# Zio_16_Servo_Controller.net
KiCad netlist of a schematic drawn in EAGLE
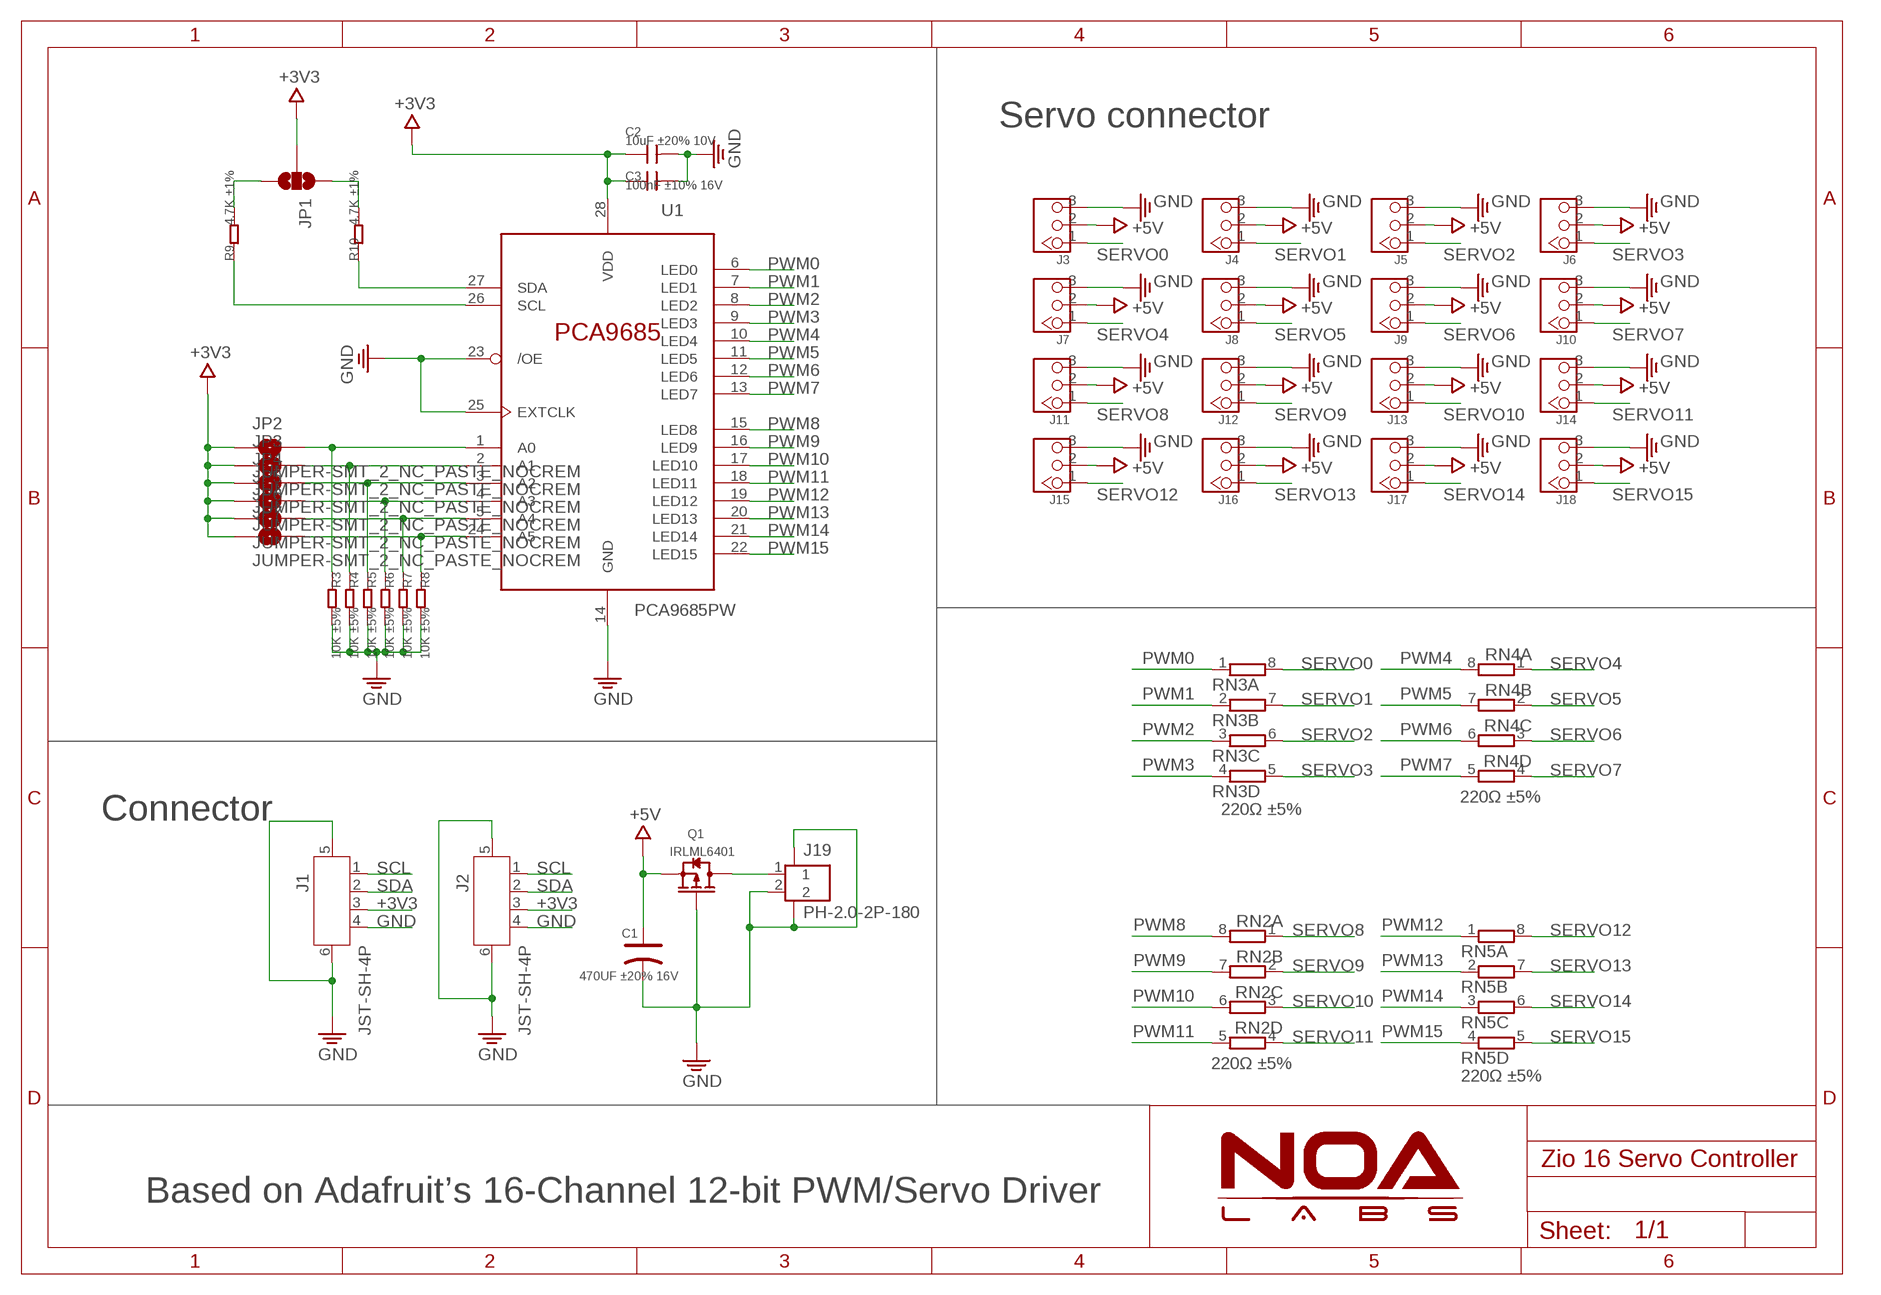
[diagram p0: schematic, sheet 1]

(export (version "E")
  (design (tool "Eeschema 10.0.6"))
  (components
    (comp (ref "C1")
      (value "470UF ±20% 16V")
      (footprint "eagle-import:ELECTRO-SMD-E-7.8MM")
      (libsource (lib "eagle-import") (part "CAP-ELECTRO-E"))
    )
    (comp (ref "C2")
      (value "10uF ±20% 10V")
      (footprint "eagle-import:0402")
      (libsource (lib "eagle-import") (part "C-0402"))
    )
    (comp (ref "C3")
      (value "100nF ±10% 16V")
      (footprint "eagle-import:0402")
      (libsource (lib "eagle-import") (part "C-0402"))
    )
    (comp (ref "J1")
      (value "JST-SH-4P")
      (footprint "eagle-import:JST-SH-4P-90")
      (libsource (lib "eagle-import") (part "JST-SH-4P"))
    )
    (comp (ref "J2")
      (value "JST-SH-4P")
      (footprint "eagle-import:JST-SH-4P-90")
      (libsource (lib "eagle-import") (part "JST-SH-4P"))
    )
    (comp (ref "J3")
      (value "HEADER-3P-2.54")
      (footprint "eagle-import:3P-2.54")
      (libsource (lib "eagle-import") (part "HEADER-3P-2.54"))
    )
    (comp (ref "J4")
      (value "HEADER-3P-2.54")
      (footprint "eagle-import:3P-2.54")
      (libsource (lib "eagle-import") (part "HEADER-3P-2.54"))
    )
    (comp (ref "J5")
      (value "HEADER-3P-2.54")
      (footprint "eagle-import:3P-2.54")
      (libsource (lib "eagle-import") (part "HEADER-3P-2.54"))
    )
    (comp (ref "J6")
      (value "HEADER-3P-2.54")
      (footprint "eagle-import:3P-2.54")
      (libsource (lib "eagle-import") (part "HEADER-3P-2.54"))
    )
    (comp (ref "J7")
      (value "HEADER-3P-2.54")
      (footprint "eagle-import:3P-2.54")
      (libsource (lib "eagle-import") (part "HEADER-3P-2.54"))
    )
    (comp (ref "J8")
      (value "HEADER-3P-2.54")
      (footprint "eagle-import:3P-2.54")
      (libsource (lib "eagle-import") (part "HEADER-3P-2.54"))
    )
    (comp (ref "J9")
      (value "HEADER-3P-2.54")
      (footprint "eagle-import:3P-2.54")
      (libsource (lib "eagle-import") (part "HEADER-3P-2.54"))
    )
    (comp (ref "J10")
      (value "HEADER-3P-2.54")
      (footprint "eagle-import:3P-2.54")
      (libsource (lib "eagle-import") (part "HEADER-3P-2.54"))
    )
    (comp (ref "J11")
      (value "HEADER-3P-2.54")
      (footprint "eagle-import:3P-2.54")
      (libsource (lib "eagle-import") (part "HEADER-3P-2.54"))
    )
    (comp (ref "J12")
      (value "HEADER-3P-2.54")
      (footprint "eagle-import:3P-2.54")
      (libsource (lib "eagle-import") (part "HEADER-3P-2.54"))
    )
    (comp (ref "J13")
      (value "HEADER-3P-2.54")
      (footprint "eagle-import:3P-2.54")
      (libsource (lib "eagle-import") (part "HEADER-3P-2.54"))
    )
    (comp (ref "J14")
      (value "HEADER-3P-2.54")
      (footprint "eagle-import:3P-2.54")
      (libsource (lib "eagle-import") (part "HEADER-3P-2.54"))
    )
    (comp (ref "J15")
      (value "HEADER-3P-2.54")
      (footprint "eagle-import:3P-2.54")
      (libsource (lib "eagle-import") (part "HEADER-3P-2.54"))
    )
    (comp (ref "J16")
      (value "HEADER-3P-2.54")
      (footprint "eagle-import:3P-2.54")
      (libsource (lib "eagle-import") (part "HEADER-3P-2.54"))
    )
    (comp (ref "J17")
      (value "HEADER-3P-2.54")
      (footprint "eagle-import:3P-2.54")
      (libsource (lib "eagle-import") (part "HEADER-3P-2.54"))
    )
    (comp (ref "J18")
      (value "HEADER-3P-2.54")
      (footprint "eagle-import:3P-2.54")
      (libsource (lib "eagle-import") (part "HEADER-3P-2.54"))
    )
    (comp (ref "J19")
      (value "PH-2.0-2P-180")
      (footprint "eagle-import:PH2.0_2P_180")
      (libsource (lib "eagle-import") (part "PH-2.0-2P-180"))
    )
    (comp (ref "JP1")
      (value "JUMPER-SMT_3_2-NC_PASTE_NOCREM")
      (footprint "eagle-import:SMT-JUMPER_3_2-NC_PASTE_SILK_NOCREM")
      (libsource (lib "eagle-import") (part "JUMPER-SMT_3_2-NC_PASTE_NOCREM"))
    )
    (comp (ref "JP2")
      (value "JUMPER-SMT_2_NC_PASTE_NOCREM")
      (footprint "eagle-import:SMT-JUMPER_2_NC_PASTE_SILK_NOCREM")
      (libsource (lib "eagle-import") (part "JUMPER-SMT_2_NC_PASTE_NOCREM"))
    )
    (comp (ref "JP3")
      (value "JUMPER-SMT_2_NC_PASTE_NOCREM")
      (footprint "eagle-import:SMT-JUMPER_2_NC_PASTE_SILK_NOCREM")
      (libsource (lib "eagle-import") (part "JUMPER-SMT_2_NC_PASTE_NOCREM"))
    )
    (comp (ref "JP4")
      (value "JUMPER-SMT_2_NC_PASTE_NOCREM")
      (footprint "eagle-import:SMT-JUMPER_2_NC_PASTE_SILK_NOCREM")
      (libsource (lib "eagle-import") (part "JUMPER-SMT_2_NC_PASTE_NOCREM"))
    )
    (comp (ref "JP5")
      (value "JUMPER-SMT_2_NC_PASTE_NOCREM")
      (footprint "eagle-import:SMT-JUMPER_2_NC_PASTE_SILK_NOCREM")
      (libsource (lib "eagle-import") (part "JUMPER-SMT_2_NC_PASTE_NOCREM"))
    )
    (comp (ref "JP6")
      (value "JUMPER-SMT_2_NC_PASTE_NOCREM")
      (footprint "eagle-import:SMT-JUMPER_2_NC_PASTE_SILK_NOCREM")
      (libsource (lib "eagle-import") (part "JUMPER-SMT_2_NC_PASTE_NOCREM"))
    )
    (comp (ref "JP7")
      (value "JUMPER-SMT_2_NC_PASTE_NOCREM")
      (footprint "eagle-import:SMT-JUMPER_2_NC_PASTE_SILK_NOCREM")
      (libsource (lib "eagle-import") (part "JUMPER-SMT_2_NC_PASTE_NOCREM"))
    )
    (comp (ref "Q1")
      (value "IRLML6401")
      (footprint "eagle-import:SOT23")
      (libsource (lib "eagle-import") (part "MOSFET-P-SOT23"))
    )
    (comp (ref "R3")
      (value "10K ±5%")
      (footprint "eagle-import:0402")
      (libsource (lib "eagle-import") (part "R-0402"))
    )
    (comp (ref "R4")
      (value "10K ±5%")
      (footprint "eagle-import:0402")
      (libsource (lib "eagle-import") (part "R-0402"))
    )
    (comp (ref "R5")
      (value "10K ±5%")
      (footprint "eagle-import:0402")
      (libsource (lib "eagle-import") (part "R-0402"))
    )
    (comp (ref "R6")
      (value "10K ±5%")
      (footprint "eagle-import:0402")
      (libsource (lib "eagle-import") (part "R-0402"))
    )
    (comp (ref "R7")
      (value "10K ±5%")
      (footprint "eagle-import:0402")
      (libsource (lib "eagle-import") (part "R-0402"))
    )
    (comp (ref "R8")
      (value "10K ±5%")
      (footprint "eagle-import:0402")
      (libsource (lib "eagle-import") (part "R-0402"))
    )
    (comp (ref "R9")
      (value "4.7K ±1%")
      (footprint "eagle-import:0402")
      (libsource (lib "eagle-import") (part "Discretex_R-0402"))
    )
    (comp (ref "R10")
      (value "4.7K ±1%")
      (footprint "eagle-import:0402")
      (libsource (lib "eagle-import") (part "Discretex_R-0402"))
    )
    (comp (ref "RN2")
      (value "220Ω ±5%")
      (footprint "eagle-import:RESISTOR-DIL_0603-ARV")
      (libsource (lib "eagle-import") (part "RESISTOR-DIL_4R-N0603-ARV"))
    )
    (comp (ref "RN3")
      (value "220Ω ±5%")
      (footprint "eagle-import:RESISTOR-DIL_0603-ARV")
      (libsource (lib "eagle-import") (part "RESISTOR-DIL_4R-N0603-ARV"))
    )
    (comp (ref "RN4")
      (value "220Ω ±5%")
      (footprint "eagle-import:RESISTOR-DIL_0603-ARV")
      (libsource (lib "eagle-import") (part "RESISTOR-DIL_4R-N0603-ARV"))
    )
    (comp (ref "RN5")
      (value "220Ω ±5%")
      (footprint "eagle-import:RESISTOR-DIL_0603-ARV")
      (libsource (lib "eagle-import") (part "RESISTOR-DIL_4R-N0603-ARV"))
    )
    (comp (ref "U1")
      (value "PCA9685PW")
      (footprint "eagle-import:TSSOP28")
      (libsource (lib "eagle-import") (part "PCA9685PW"))
    )
  )
  (nets
    (net (code "1") (name "+3V3") (class "Default")
      (node (ref "C2") (pin "1") (pinfunction "1_1") (pintype "passive"))
      (node (ref "C3") (pin "1") (pinfunction "1_1") (pintype "passive"))
      (node (ref "J1") (pin "3") (pinfunction "3_3") (pintype "bidirectional"))
      (node (ref "J2") (pin "3") (pinfunction "3_3") (pintype "bidirectional"))
      (node (ref "JP1") (pin "2") (pinfunction "2_2") (pintype "passive"))
      (node (ref "JP2") (pin "1") (pinfunction "1_1") (pintype "passive"))
      (node (ref "JP3") (pin "1") (pinfunction "1_1") (pintype "passive"))
      (node (ref "JP4") (pin "1") (pinfunction "1_1") (pintype "passive"))
      (node (ref "JP5") (pin "1") (pinfunction "1_1") (pintype "passive"))
      (node (ref "JP6") (pin "1") (pinfunction "1_1") (pintype "passive"))
      (node (ref "JP7") (pin "1") (pinfunction "1_1") (pintype "passive"))
      (node (ref "U1") (pin "28") (pinfunction "VDD_28") (pintype "power_in"))
    )
    (net (code "2") (name "+5V") (class "Default")
      (node (ref "C1") (pin "+") (pinfunction "+_+") (pintype "passive"))
      (node (ref "J10") (pin "2") (pinfunction "P$2_2") (pintype "bidirectional"))
      (node (ref "J11") (pin "2") (pinfunction "P$2_2") (pintype "bidirectional"))
      (node (ref "J12") (pin "2") (pinfunction "P$2_2") (pintype "bidirectional"))
      (node (ref "J13") (pin "2") (pinfunction "P$2_2") (pintype "bidirectional"))
      (node (ref "J14") (pin "2") (pinfunction "P$2_2") (pintype "bidirectional"))
      (node (ref "J15") (pin "2") (pinfunction "P$2_2") (pintype "bidirectional"))
      (node (ref "J16") (pin "2") (pinfunction "P$2_2") (pintype "bidirectional"))
      (node (ref "J17") (pin "2") (pinfunction "P$2_2") (pintype "bidirectional"))
      (node (ref "J18") (pin "2") (pinfunction "P$2_2") (pintype "bidirectional"))
      (node (ref "J3") (pin "2") (pinfunction "P$2_2") (pintype "bidirectional"))
      (node (ref "J4") (pin "2") (pinfunction "P$2_2") (pintype "bidirectional"))
      (node (ref "J5") (pin "2") (pinfunction "P$2_2") (pintype "bidirectional"))
      (node (ref "J6") (pin "2") (pinfunction "P$2_2") (pintype "bidirectional"))
      (node (ref "J7") (pin "2") (pinfunction "P$2_2") (pintype "bidirectional"))
      (node (ref "J8") (pin "2") (pinfunction "P$2_2") (pintype "bidirectional"))
      (node (ref "J9") (pin "2") (pinfunction "P$2_2") (pintype "bidirectional"))
      (node (ref "Q1") (pin "2") (pinfunction "S_2") (pintype "passive"))
    )
    (net (code "3") (name "/PWM0") (class "Default")
      (node (ref "RN3") (pin "1") (pinfunction "1_1") (pintype "passive"))
      (node (ref "U1") (pin "6") (pinfunction "LED0_6") (pintype "bidirectional"))
    )
    (net (code "4") (name "/PWM1") (class "Default")
      (node (ref "RN3") (pin "2") (pinfunction "1_2") (pintype "passive"))
      (node (ref "U1") (pin "7") (pinfunction "LED1_7") (pintype "bidirectional"))
    )
    (net (code "5") (name "/PWM2") (class "Default")
      (node (ref "RN3") (pin "3") (pinfunction "1_3") (pintype "passive"))
      (node (ref "U1") (pin "8") (pinfunction "LED2_8") (pintype "bidirectional"))
    )
    (net (code "6") (name "/PWM3") (class "Default")
      (node (ref "RN3") (pin "4") (pinfunction "1_4") (pintype "passive"))
      (node (ref "U1") (pin "9") (pinfunction "LED3_9") (pintype "bidirectional"))
    )
    (net (code "7") (name "/PWM4") (class "Default")
      (node (ref "RN4") (pin "8") (pinfunction "2_8") (pintype "passive"))
      (node (ref "U1") (pin "10") (pinfunction "LED4_10") (pintype "bidirectional"))
    )
    (net (code "8") (name "/PWM5") (class "Default")
      (node (ref "RN4") (pin "7") (pinfunction "2_7") (pintype "passive"))
      (node (ref "U1") (pin "11") (pinfunction "LED5_11") (pintype "bidirectional"))
    )
    (net (code "9") (name "/PWM6") (class "Default")
      (node (ref "RN4") (pin "6") (pinfunction "2_6") (pintype "passive"))
      (node (ref "U1") (pin "12") (pinfunction "LED6_12") (pintype "bidirectional"))
    )
    (net (code "10") (name "/PWM7") (class "Default")
      (node (ref "RN4") (pin "5") (pinfunction "2_5") (pintype "passive"))
      (node (ref "U1") (pin "13") (pinfunction "LED7_13") (pintype "bidirectional"))
    )
    (net (code "11") (name "/PWM8") (class "Default")
      (node (ref "RN2") (pin "8") (pinfunction "2_8") (pintype "passive"))
      (node (ref "U1") (pin "15") (pinfunction "LED8_15") (pintype "bidirectional"))
    )
    (net (code "12") (name "/PWM9") (class "Default")
      (node (ref "RN2") (pin "7") (pinfunction "2_7") (pintype "passive"))
      (node (ref "U1") (pin "16") (pinfunction "LED9_16") (pintype "bidirectional"))
    )
    (net (code "13") (name "/PWM10") (class "Default")
      (node (ref "RN2") (pin "6") (pinfunction "2_6") (pintype "passive"))
      (node (ref "U1") (pin "17") (pinfunction "LED10_17") (pintype "bidirectional"))
    )
    (net (code "14") (name "/PWM11") (class "Default")
      (node (ref "RN2") (pin "5") (pinfunction "2_5") (pintype "passive"))
      (node (ref "U1") (pin "18") (pinfunction "LED11_18") (pintype "bidirectional"))
    )
    (net (code "15") (name "/PWM12") (class "Default")
      (node (ref "RN5") (pin "1") (pinfunction "1_1") (pintype "passive"))
      (node (ref "U1") (pin "19") (pinfunction "LED12_19") (pintype "bidirectional"))
    )
    (net (code "16") (name "/PWM13") (class "Default")
      (node (ref "RN5") (pin "2") (pinfunction "1_2") (pintype "passive"))
      (node (ref "U1") (pin "20") (pinfunction "LED13_20") (pintype "bidirectional"))
    )
    (net (code "17") (name "/PWM14") (class "Default")
      (node (ref "RN5") (pin "3") (pinfunction "1_3") (pintype "passive"))
      (node (ref "U1") (pin "21") (pinfunction "LED14_21") (pintype "bidirectional"))
    )
    (net (code "18") (name "/PWM15") (class "Default")
      (node (ref "RN5") (pin "4") (pinfunction "1_4") (pintype "passive"))
      (node (ref "U1") (pin "22") (pinfunction "LED15_22") (pintype "bidirectional"))
    )
    (net (code "19") (name "/SCL") (class "Default")
      (node (ref "J1") (pin "1") (pinfunction "1_1") (pintype "bidirectional"))
      (node (ref "J2") (pin "1") (pinfunction "1_1") (pintype "bidirectional"))
      (node (ref "R9") (pin "1") (pinfunction "1_1") (pintype "passive"))
      (node (ref "U1") (pin "26") (pinfunction "SCL_26") (pintype "bidirectional"))
    )
    (net (code "20") (name "/SDA") (class "Default")
      (node (ref "J1") (pin "2") (pinfunction "2_2") (pintype "bidirectional"))
      (node (ref "J2") (pin "2") (pinfunction "2_2") (pintype "bidirectional"))
      (node (ref "R10") (pin "1") (pinfunction "1_1") (pintype "passive"))
      (node (ref "U1") (pin "27") (pinfunction "SDA_27") (pintype "bidirectional"))
    )
    (net (code "21") (name "/SERVO0") (class "Default")
      (node (ref "J3") (pin "1") (pinfunction "P$1_1") (pintype "bidirectional"))
      (node (ref "RN3") (pin "8") (pinfunction "2_8") (pintype "passive"))
    )
    (net (code "22") (name "/SERVO1") (class "Default")
      (node (ref "J4") (pin "1") (pinfunction "P$1_1") (pintype "bidirectional"))
      (node (ref "RN3") (pin "7") (pinfunction "2_7") (pintype "passive"))
    )
    (net (code "23") (name "/SERVO2") (class "Default")
      (node (ref "J5") (pin "1") (pinfunction "P$1_1") (pintype "bidirectional"))
      (node (ref "RN3") (pin "6") (pinfunction "2_6") (pintype "passive"))
    )
    (net (code "24") (name "/SERVO3") (class "Default")
      (node (ref "J6") (pin "1") (pinfunction "P$1_1") (pintype "bidirectional"))
      (node (ref "RN3") (pin "5") (pinfunction "2_5") (pintype "passive"))
    )
    (net (code "25") (name "/SERVO4") (class "Default")
      (node (ref "J7") (pin "1") (pinfunction "P$1_1") (pintype "bidirectional"))
      (node (ref "RN4") (pin "1") (pinfunction "1_1") (pintype "passive"))
    )
    (net (code "26") (name "/SERVO5") (class "Default")
      (node (ref "J8") (pin "1") (pinfunction "P$1_1") (pintype "bidirectional"))
      (node (ref "RN4") (pin "2") (pinfunction "1_2") (pintype "passive"))
    )
    (net (code "27") (name "/SERVO6") (class "Default")
      (node (ref "J9") (pin "1") (pinfunction "P$1_1") (pintype "bidirectional"))
      (node (ref "RN4") (pin "3") (pinfunction "1_3") (pintype "passive"))
    )
    (net (code "28") (name "/SERVO7") (class "Default")
      (node (ref "J10") (pin "1") (pinfunction "P$1_1") (pintype "bidirectional"))
      (node (ref "RN4") (pin "4") (pinfunction "1_4") (pintype "passive"))
    )
    (net (code "29") (name "/SERVO8") (class "Default")
      (node (ref "J11") (pin "1") (pinfunction "P$1_1") (pintype "bidirectional"))
      (node (ref "RN2") (pin "1") (pinfunction "1_1") (pintype "passive"))
    )
    (net (code "30") (name "/SERVO9") (class "Default")
      (node (ref "J12") (pin "1") (pinfunction "P$1_1") (pintype "bidirectional"))
      (node (ref "RN2") (pin "2") (pinfunction "1_2") (pintype "passive"))
    )
    (net (code "31") (name "/SERVO10") (class "Default")
      (node (ref "J13") (pin "1") (pinfunction "P$1_1") (pintype "bidirectional"))
      (node (ref "RN2") (pin "3") (pinfunction "1_3") (pintype "passive"))
    )
    (net (code "32") (name "/SERVO11") (class "Default")
      (node (ref "J14") (pin "1") (pinfunction "P$1_1") (pintype "bidirectional"))
      (node (ref "RN2") (pin "4") (pinfunction "1_4") (pintype "passive"))
    )
    (net (code "33") (name "/SERVO12") (class "Default")
      (node (ref "J15") (pin "1") (pinfunction "P$1_1") (pintype "bidirectional"))
      (node (ref "RN5") (pin "8") (pinfunction "2_8") (pintype "passive"))
    )
    (net (code "34") (name "/SERVO13") (class "Default")
      (node (ref "J16") (pin "1") (pinfunction "P$1_1") (pintype "bidirectional"))
      (node (ref "RN5") (pin "7") (pinfunction "2_7") (pintype "passive"))
    )
    (net (code "35") (name "/SERVO14") (class "Default")
      (node (ref "J17") (pin "1") (pinfunction "P$1_1") (pintype "bidirectional"))
      (node (ref "RN5") (pin "6") (pinfunction "2_6") (pintype "passive"))
    )
    (net (code "36") (name "/SERVO15") (class "Default")
      (node (ref "J18") (pin "1") (pinfunction "P$1_1") (pintype "bidirectional"))
      (node (ref "RN5") (pin "5") (pinfunction "2_5") (pintype "passive"))
    )
    (net (code "37") (name "GND") (class "Default")
      (node (ref "C1") (pin "-") (pinfunction "-_-") (pintype "passive"))
      (node (ref "C2") (pin "2") (pinfunction "2_2") (pintype "passive"))
      (node (ref "C3") (pin "2") (pinfunction "2_2") (pintype "passive"))
      (node (ref "J1") (pin "4") (pinfunction "4_4") (pintype "bidirectional"))
      (node (ref "J1") (pin "5") (pinfunction "5_5") (pintype "bidirectional"))
      (node (ref "J1") (pin "6") (pinfunction "6_6") (pintype "bidirectional"))
      (node (ref "J10") (pin "3") (pinfunction "P$3_3") (pintype "bidirectional"))
      (node (ref "J11") (pin "3") (pinfunction "P$3_3") (pintype "bidirectional"))
      (node (ref "J12") (pin "3") (pinfunction "P$3_3") (pintype "bidirectional"))
      (node (ref "J13") (pin "3") (pinfunction "P$3_3") (pintype "bidirectional"))
      (node (ref "J14") (pin "3") (pinfunction "P$3_3") (pintype "bidirectional"))
      (node (ref "J15") (pin "3") (pinfunction "P$3_3") (pintype "bidirectional"))
      (node (ref "J16") (pin "3") (pinfunction "P$3_3") (pintype "bidirectional"))
      (node (ref "J17") (pin "3") (pinfunction "P$3_3") (pintype "bidirectional"))
      (node (ref "J18") (pin "3") (pinfunction "P$3_3") (pintype "bidirectional"))
      (node (ref "J19") (pin "2") (pinfunction "2_2") (pintype "bidirectional"))
      (node (ref "J19") (pin "3") (pinfunction "3_3") (pintype "bidirectional"))
      (node (ref "J19") (pin "4") (pinfunction "4_4") (pintype "bidirectional"))
      (node (ref "J2") (pin "4") (pinfunction "4_4") (pintype "bidirectional"))
      (node (ref "J2") (pin "5") (pinfunction "5_5") (pintype "bidirectional"))
      (node (ref "J2") (pin "6") (pinfunction "6_6") (pintype "bidirectional"))
      (node (ref "J3") (pin "3") (pinfunction "P$3_3") (pintype "bidirectional"))
      (node (ref "J4") (pin "3") (pinfunction "P$3_3") (pintype "bidirectional"))
      (node (ref "J5") (pin "3") (pinfunction "P$3_3") (pintype "bidirectional"))
      (node (ref "J6") (pin "3") (pinfunction "P$3_3") (pintype "bidirectional"))
      (node (ref "J7") (pin "3") (pinfunction "P$3_3") (pintype "bidirectional"))
      (node (ref "J8") (pin "3") (pinfunction "P$3_3") (pintype "bidirectional"))
      (node (ref "J9") (pin "3") (pinfunction "P$3_3") (pintype "bidirectional"))
      (node (ref "Q1") (pin "1") (pinfunction "G_1") (pintype "passive"))
      (node (ref "R3") (pin "2") (pinfunction "2_2") (pintype "passive"))
      (node (ref "R4") (pin "2") (pinfunction "2_2") (pintype "passive"))
      (node (ref "R5") (pin "2") (pinfunction "2_2") (pintype "passive"))
      (node (ref "R6") (pin "2") (pinfunction "2_2") (pintype "passive"))
      (node (ref "R7") (pin "2") (pinfunction "2_2") (pintype "passive"))
      (node (ref "R8") (pin "2") (pinfunction "2_2") (pintype "passive"))
      (node (ref "U1") (pin "14") (pinfunction "GND_14") (pintype "power_in"))
      (node (ref "U1") (pin "23") (pinfunction "/OE_23") (pintype "bidirectional"))
      (node (ref "U1") (pin "25") (pinfunction "EXTCLK_25") (pintype "input"))
    )
    (net (code "38") (name "Net-(JP1-Pad1)") (class "Default")
      (node (ref "JP1") (pin "1") (pinfunction "1_1") (pintype "passive"))
      (node (ref "R10") (pin "2") (pinfunction "2_2") (pintype "passive"))
    )
    (net (code "39") (name "Net-(JP1-Pad3)") (class "Default")
      (node (ref "JP1") (pin "3") (pinfunction "3_3") (pintype "passive"))
      (node (ref "R9") (pin "2") (pinfunction "2_2") (pintype "passive"))
    )
    (net (code "40") (name "Net-(Q1-D)") (class "Default")
      (node (ref "J19") (pin "1") (pinfunction "1_1") (pintype "bidirectional"))
      (node (ref "Q1") (pin "3") (pinfunction "D_3") (pintype "passive"))
    )
    (net (code "41") (name "Net-(U1-A0)") (class "Default")
      (node (ref "JP2") (pin "2") (pinfunction "2_2") (pintype "passive"))
      (node (ref "R3") (pin "1") (pinfunction "1_1") (pintype "passive"))
      (node (ref "U1") (pin "1") (pinfunction "A0_1") (pintype "bidirectional"))
    )
    (net (code "42") (name "Net-(U1-A1)") (class "Default")
      (node (ref "JP3") (pin "2") (pinfunction "2_2") (pintype "passive"))
      (node (ref "R4") (pin "1") (pinfunction "1_1") (pintype "passive"))
      (node (ref "U1") (pin "2") (pinfunction "A1_2") (pintype "bidirectional"))
    )
    (net (code "43") (name "Net-(U1-A2)") (class "Default")
      (node (ref "JP4") (pin "2") (pinfunction "2_2") (pintype "passive"))
      (node (ref "R5") (pin "1") (pinfunction "1_1") (pintype "passive"))
      (node (ref "U1") (pin "3") (pinfunction "A2_3") (pintype "bidirectional"))
    )
    (net (code "44") (name "Net-(U1-A3)") (class "Default")
      (node (ref "JP5") (pin "2") (pinfunction "2_2") (pintype "passive"))
      (node (ref "R6") (pin "1") (pinfunction "1_1") (pintype "passive"))
      (node (ref "U1") (pin "4") (pinfunction "A3_4") (pintype "bidirectional"))
    )
    (net (code "45") (name "Net-(U1-A4)") (class "Default")
      (node (ref "JP6") (pin "2") (pinfunction "2_2") (pintype "passive"))
      (node (ref "R7") (pin "1") (pinfunction "1_1") (pintype "passive"))
      (node (ref "U1") (pin "5") (pinfunction "A4_5") (pintype "bidirectional"))
    )
    (net (code "46") (name "Net-(U1-A5)") (class "Default")
      (node (ref "JP7") (pin "2") (pinfunction "2_2") (pintype "passive"))
      (node (ref "R8") (pin "1") (pinfunction "1_1") (pintype "passive"))
      (node (ref "U1") (pin "24") (pinfunction "A5_24") (pintype "bidirectional"))
    )
  )
)
